# Top.net
KiCad netlist of a schematic drawn in Altium Designer
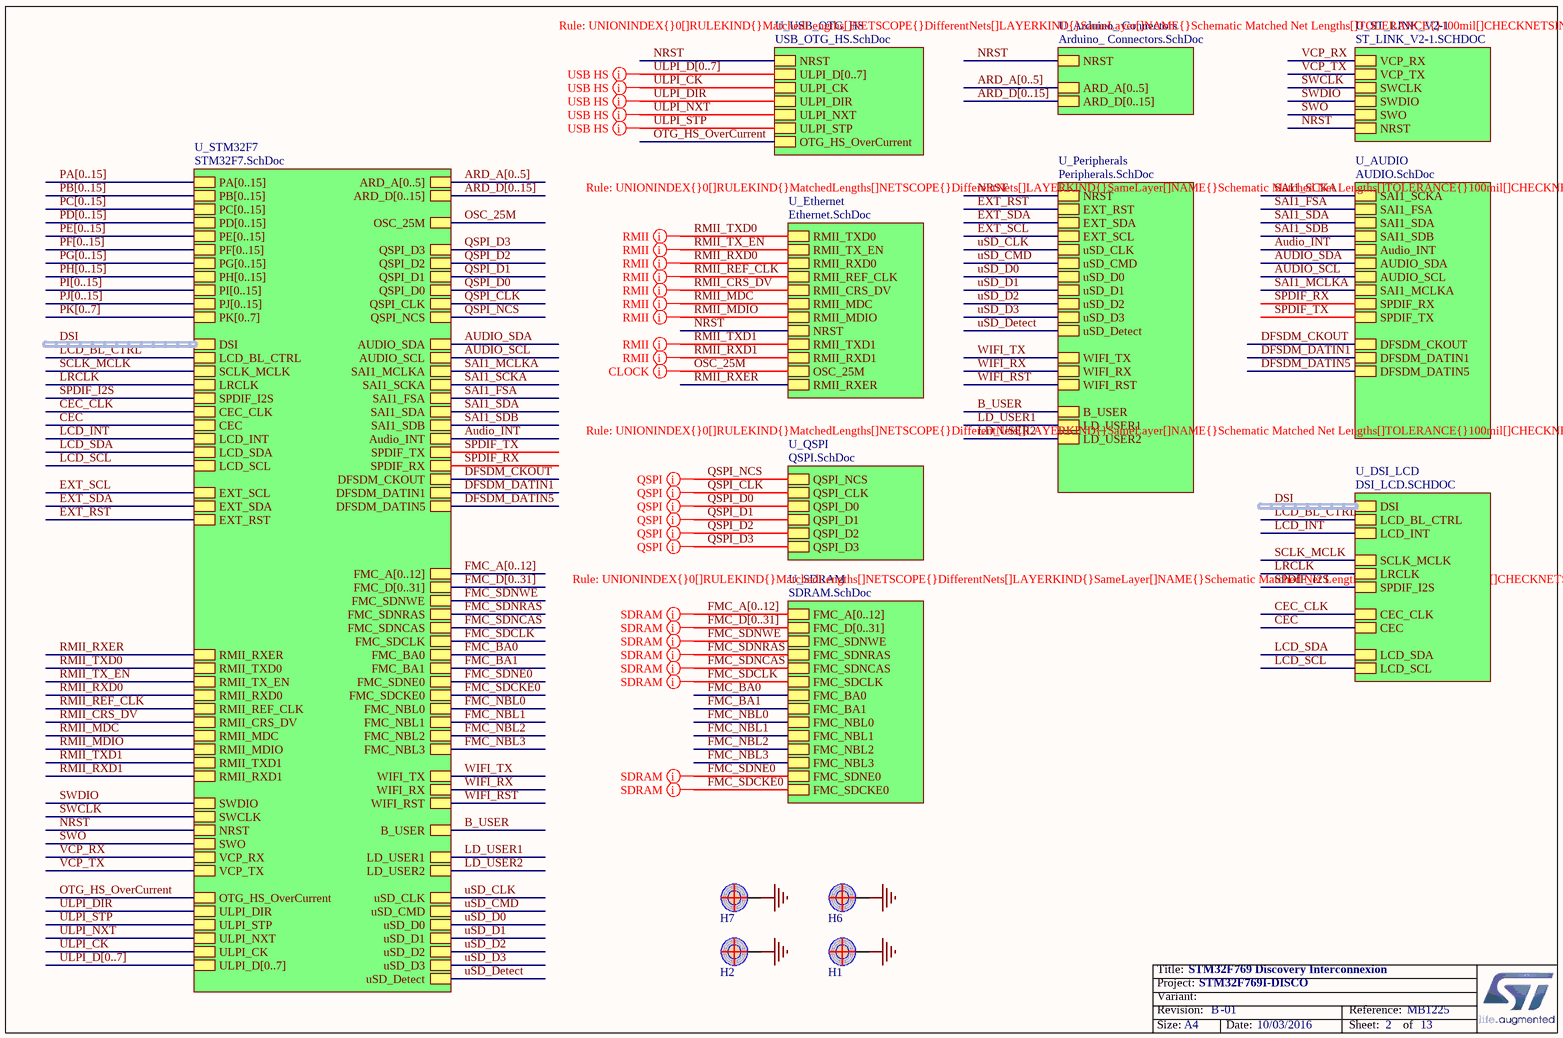
[diagram p0: Top.SchDoc]

(export (version "E")
  (design (tool "Eeschema 10.0.6"))
  (components
    (comp (ref "H1")
      (value "POSITION HOLE C6D3R5")
      (footprint "HOLE_C6D3R5")
      (libsource (lib "MCD_TOOLS_MISCELLANEOUS") (part "POSITION HOLE C6D3R5"))
    )
    (comp (ref "H2")
      (value "POSITION HOLE C6D3R5")
      (footprint "HOLE_C6D3R5")
      (libsource (lib "MCD_TOOLS_MISCELLANEOUS") (part "POSITION HOLE C6D3R5"))
    )
    (comp (ref "H6")
      (value "POSITION HOLE C6D3R5")
      (footprint "HOLE_C6D3R5")
      (libsource (lib "MCD_TOOLS_MISCELLANEOUS") (part "POSITION HOLE C6D3R5"))
    )
    (comp (ref "H7")
      (value "POSITION HOLE C6D3R5")
      (footprint "HOLE_C6D3R5")
      (libsource (lib "MCD_TOOLS_MISCELLANEOUS") (part "POSITION HOLE C6D3R5"))
    )
  )
  (nets
    (net (code "340") (name "GND") (class "Default")
      (node (ref "H1") (pin "1") (pinfunction "1_1") (pintype "passive"))
      (node (ref "H2") (pin "1") (pinfunction "1_1") (pintype "passive"))
      (node (ref "H6") (pin "1") (pinfunction "1_1") (pintype "passive"))
      (node (ref "H7") (pin "1") (pinfunction "1_1") (pintype "passive"))
    )
  )
)
